# Schematic_R2_5.net
KiCad netlist of a schematic drawn in Altium Designer
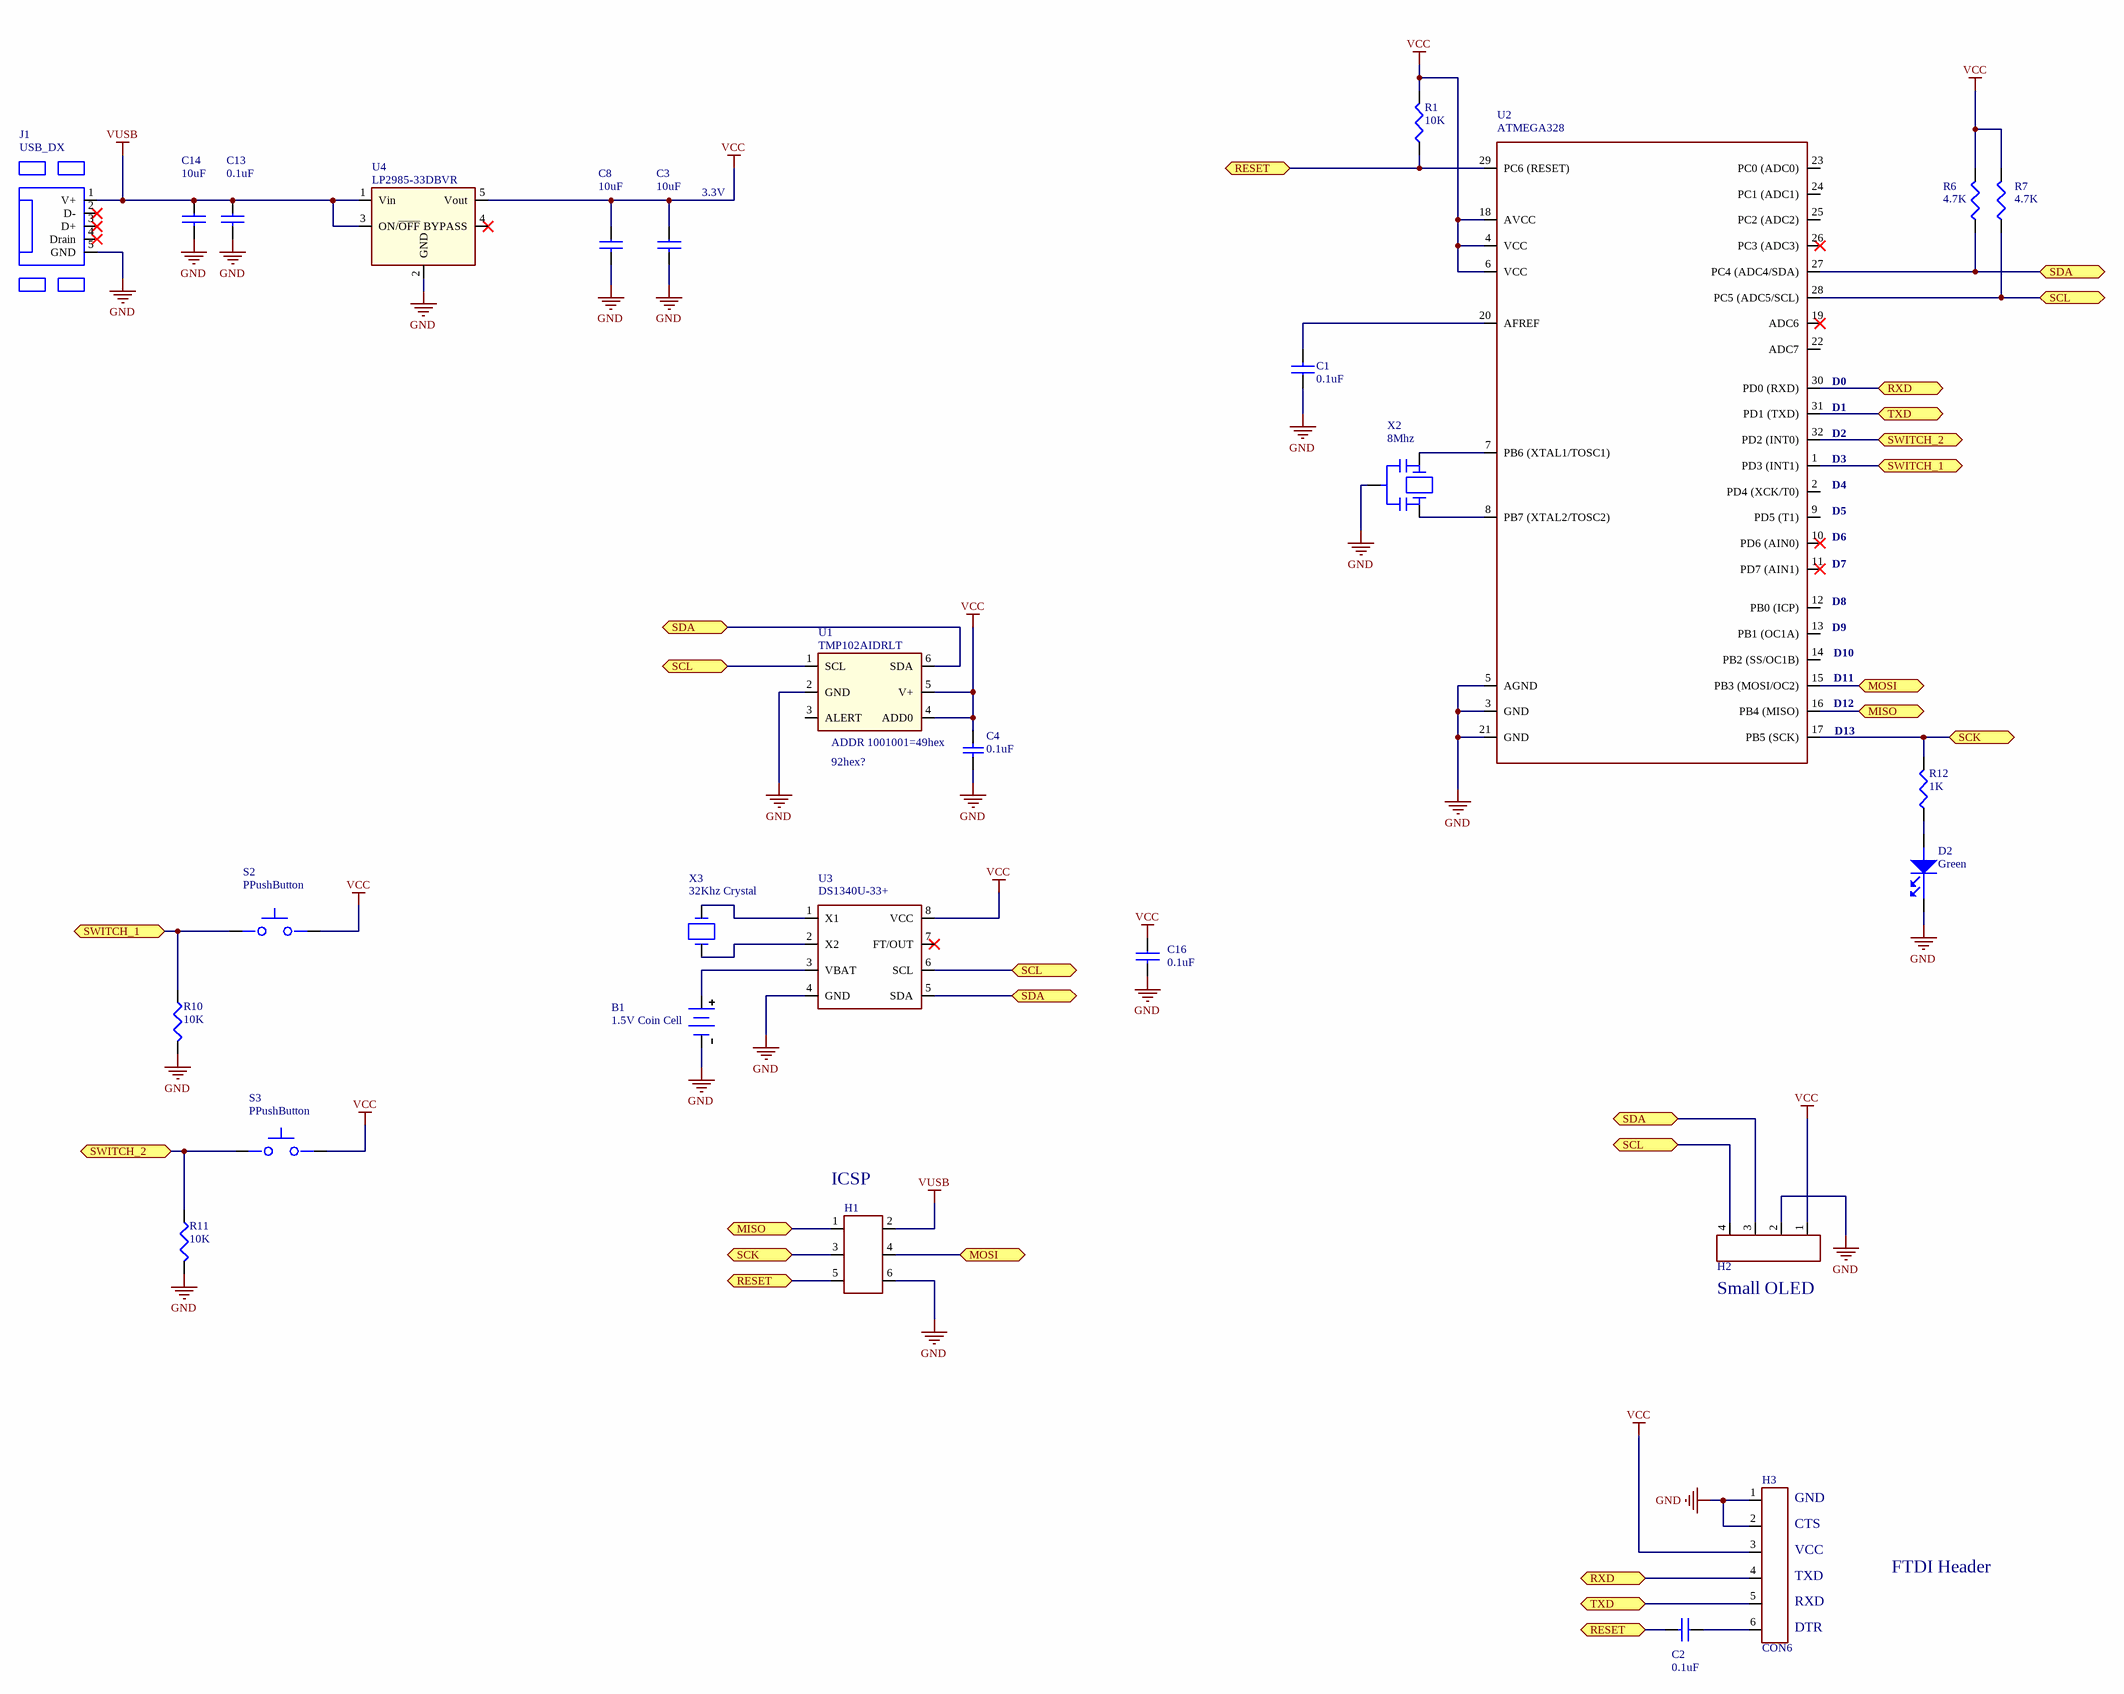
[diagram p0: Schematic_R2.5.SchDoc]

(export (version "E")
  (design (tool "Eeschema 10.0.6"))
  (components
    (comp (ref "B1")
      (value "1.5V Coin Cell")
      (footprint "CR377 Mount")
      (description "Custom CR377 mount")
      (fields (field (name "MANUFACTURER") "Sunbeam") (field (name "Comment") "CR377"))
      (libsource (lib "MAR") (part "CR377"))
    )
    (comp (ref "C1")
      (value "0.1uF")
      (footprint "CAPC1608X90N")
      (description "CAP CER 0.1uF, 0603")
      (libsource (lib "Parts_Library") (part "CAP_0603"))
    )
    (comp (ref "C2")
      (value "0.1uF")
      (footprint "CAPC1608X90N")
      (description "CAP CER 0.1uF, 0603")
      (libsource (lib "Parts_Library") (part "CAP_0603"))
    )
    (comp (ref "C3")
      (value "10uF")
      (footprint "CAPC3216X160N")
      (description "CAP_1206")
      (libsource (lib "MAR") (part "CAP_1206"))
    )
    (comp (ref "C4")
      (value "0.1uF")
      (footprint "CAPC1608X09L")
      (description "CAP CER 0.1UF 50V 10% X7R 0603")
      (fields (field (name "PARTNUMBER") "GRM188R71H104KA93D") (field (name "MANUFACTURER") "Murata"))
      (libsource (lib "Miscellaneous Devices") (part "Cap Semi"))
    )
    (comp (ref "C8")
      (value "10uF")
      (footprint "CAPC3216X160N")
      (description "CAP_1206")
      (libsource (lib "MAR") (part "CAP_1206"))
    )
    (comp (ref "C13")
      (value "0.1uF")
      (footprint "CAPC1608X90N")
      (description "CAP 0603")
      (libsource (lib "Parts_Library") (part "CAP_0603"))
    )
    (comp (ref "C14")
      (value "10uF")
      (footprint "CAPC3216X160N")
      (description "CAP_1206")
      (libsource (lib "MAR") (part "CAP_1206"))
    )
    (comp (ref "C16")
      (value "0.1uF")
      (footprint "CAPC1608X90N")
      (description "CAP CER 0.1uF 0603")
      (libsource (lib "Parts_Library") (part "CAP_0603"))
    )
    (comp (ref "D2")
      (value "Green")
      (footprint "LED1608X55N-YELLOW")
      (description "LED_0603")
      (libsource (lib "Parts_Library") (part "LED_0603"))
    )
    (comp (ref "H1")
      (value "CON3X2")
      (footprint "HDR3X2")
      (description "CONN HEADER 3X2POS .100\" PADS")
      (fields (field (name "PARTNUMBER") "PADS"))
      (libsource (lib "Parts_Library") (part "CON3X2"))
    )
    (comp (ref "H2")
      (value "TSW-104-07-L-S")
      (footprint "HDR1X4-Empty")
      (description "CONN HEADER 4POS .100\" SGL GOLD")
      (fields (field (name "MANUFACTURER") "Samtec"))
      (libsource (lib "Parts_Library") (part "TSW-104-07-L-S"))
    )
    (comp (ref "H3")
      (value "CON6")
      (footprint "HDR1X6")
      (description "CONN HEADER 6POS .100\" PADS")
      (fields (field (name "PARTNUMBER") "PADS"))
      (libsource (lib "MAR") (part "CON6"))
    )
    (comp (ref "J1")
      (value "USB_DX")
      (footprint "USB_DX")
      (description "CONN RECEPT MINIUSB R/A 5POS SMD")
      (libsource (lib "Parts_Library") (part "USB_DX"))
    )
    (comp (ref "R1")
      (value "10K")
      (footprint "RESC1608X55N")
      (description "RES 10K, 0603")
      (libsource (lib "Parts_Library") (part "RES_0603"))
    )
    (comp (ref "R6")
      (value "4.7K")
      (footprint "RESC1608X55N")
      (description "RES 10K, 0603")
      (libsource (lib "Parts_Library") (part "RES_0603"))
    )
    (comp (ref "R7")
      (value "4.7K")
      (footprint "RESC1608X55N")
      (description "RES 10K, 0603")
      (libsource (lib "Parts_Library") (part "RES_0603"))
    )
    (comp (ref "R10")
      (value "10K")
      (footprint "RESC1608X55N")
      (description "RES 10K 0603")
      (libsource (lib "Parts_Library") (part "RES_0603"))
    )
    (comp (ref "R11")
      (value "10K")
      (footprint "RESC1608X55N")
      (description "RES 10K 0603")
      (libsource (lib "Parts_Library") (part "RES_0603"))
    )
    (comp (ref "R12")
      (value "1K")
      (footprint "RESC1608X55N")
      (description "RES 330R, 0603")
      (libsource (lib "Parts_Library") (part "RES_0603"))
    )
    (comp (ref "S2")
      (value "PPushButton")
      (footprint "SWITCH TACTILE RA- DX")
      (description "DX_MINI_TACT_SWITCH_RA")
      (libsource (lib "MAR") (part "DX_MINI_TACT_SWITCH_RA"))
    )
    (comp (ref "S3")
      (value "PPushButton")
      (footprint "SWITCH TACTILE RA- DX")
      (description "DX_MINI_TACT_SWITCH_RA")
      (libsource (lib "MAR") (part "DX_MINI_TACT_SWITCH_RA"))
    )
    (comp (ref "U1")
      (value "TMP102AIDRL")
      (footprint "SOT50P150X130-6N")
      (description "IC DGTL TEMP SENSOR LP SOT-563")
      (fields (field (name "MANUFACTURER") "Texas Instruments") (field (name "PARTNUMBER") "TMP102AIDRLT"))
      (libsource (lib "MAR") (part "TMP102AIDRL"))
    )
    (comp (ref "U2")
      (value "ATMEGA328")
      (footprint "TQFP80P700X700-32N")
      (description "MCU AVR 32K FLASH 32TQFP")
      (fields (field (name "PARTNUMBER") "ATMEGA328P-AU-ND") (field (name "MANUFACTURER") "Atmel"))
      (libsource (lib "Parts_Library") (part "ATMEGA328-AUR"))
    )
    (comp (ref "U3")
      (value "DS1340U-33+")
      (footprint "TSOP65P490X110-8N")
      (description "IC RTC SERIAL 512K 8-TSSOP")
      (fields (field (name "MANUFACTURER") "Maxim"))
      (libsource (lib "Parts_Library") (part "DS1340U-33+"))
    )
    (comp (ref "U4")
      (value "LP2985-33DBVR")
      (footprint "SOT95P280X144-5N")
      (description "IC REG LDO 3.3V .15A SOT23-5")
      (fields (field (name "MANUFACTURER") "Texas Instruments") (field (name "PARTNUMBER") "LP2985-33DBVR"))
      (libsource (lib "MAR") (part "LP2985-33DBVR"))
    )
    (comp (ref "X2")
      (value "8Mhz")
      (footprint "CSTCE")
      (description "CER RESONATOR 8.0MHZ SMD")
      (fields (field (name "PARTNUMBER") "CSTCE8M00G55-R0") (field (name "MANUFACTURER") "Murata"))
      (libsource (lib "Parts_Library") (part "CSTCE8M00G55-R0"))
    )
    (comp (ref "X3")
      (value "32Khz Crystal")
      (footprint "ECS-.327-12.5-34B")
      (description "CRYSTAL 32.768 KHZ 12.5PF SMD")
      (fields (field (name "PARTNUMBER") "ECS-.327-12.5-34B") (field (name "MANUFACTURER") "ECS"))
      (libsource (lib "Parts_Library") (part "ECS-.327-12.5-34B"))
    )
  )
  (nets
    (net (code "1") (name "/MISO") (class "Default")
      (node (ref "H1") (pin "1") (pintype "passive"))
      (node (ref "U2") (pin "16") (pinfunction "PB4_(MISO)_16") (pintype "passive"))
    )
    (net (code "2") (name "/MOSI") (class "Default")
      (node (ref "H1") (pin "4") (pintype "passive"))
      (node (ref "U2") (pin "15") (pinfunction "PB3_(MOSI/OC2)_15") (pintype "passive"))
    )
    (net (code "3") (name "/RESET") (class "Default")
      (node (ref "C2") (pin "2") (pinfunction "2_2") (pintype "passive"))
      (node (ref "H1") (pin "5") (pintype "passive"))
      (node (ref "R1") (pin "1") (pinfunction "1_1") (pintype "passive"))
      (node (ref "U2") (pin "29") (pinfunction "PC6_(RESET)_29") (pintype "passive"))
    )
    (net (code "4") (name "/RXD") (class "Default")
      (node (ref "H3") (pin "4") (pintype "passive"))
      (node (ref "U2") (pin "30") (pinfunction "PD0_(RXD)_30") (pintype "passive"))
    )
    (net (code "5") (name "/SCK") (class "Default")
      (node (ref "H1") (pin "3") (pintype "passive"))
      (node (ref "R12") (pin "2") (pinfunction "2_2") (pintype "passive"))
      (node (ref "U2") (pin "17") (pinfunction "PB5_(SCK)_17") (pintype "passive"))
    )
    (net (code "6") (name "/SCL") (class "Default")
      (node (ref "H2") (pin "4") (pintype "passive"))
      (node (ref "R7") (pin "1") (pinfunction "1_1") (pintype "passive"))
      (node (ref "U1") (pin "1") (pinfunction "SCL_1") (pintype "passive"))
      (node (ref "U2") (pin "28") (pinfunction "PC5_(ADC5/SCL)_28") (pintype "passive"))
      (node (ref "U3") (pin "6") (pinfunction "SCL_6") (pintype "passive"))
    )
    (net (code "7") (name "/SDA") (class "Default")
      (node (ref "H2") (pin "3") (pintype "passive"))
      (node (ref "R6") (pin "1") (pinfunction "1_1") (pintype "passive"))
      (node (ref "U1") (pin "6") (pinfunction "SDA_6") (pintype "passive"))
      (node (ref "U2") (pin "27") (pinfunction "PC4_(ADC4/SDA)_27") (pintype "passive"))
      (node (ref "U3") (pin "5") (pinfunction "SDA_5") (pintype "passive"))
    )
    (net (code "8") (name "/SWITCH_1") (class "Default")
      (node (ref "R10") (pin "1") (pinfunction "1_1") (pintype "passive"))
      (node (ref "S2") (pin "1") (pinfunction "A_1") (pintype "passive"))
      (node (ref "U2") (pin "1") (pinfunction "PD3_(INT1)_1") (pintype "passive"))
    )
    (net (code "9") (name "/SWITCH_2") (class "Default")
      (node (ref "R11") (pin "1") (pinfunction "1_1") (pintype "passive"))
      (node (ref "S3") (pin "2") (pinfunction "B_2") (pintype "passive"))
      (node (ref "U2") (pin "32") (pinfunction "PD2_(INT0)_32") (pintype "passive"))
    )
    (net (code "10") (name "/TXD") (class "Default")
      (node (ref "H3") (pin "5") (pintype "passive"))
      (node (ref "U2") (pin "31") (pinfunction "PD1_(TXD)_31") (pintype "passive"))
    )
    (net (code "11") (name "GND") (class "Default")
      (node (ref "B1") (pin "2") (pinfunction "-_2") (pintype "passive"))
      (node (ref "C1") (pin "1") (pinfunction "1_1") (pintype "passive"))
      (node (ref "C13") (pin "2") (pinfunction "2_2") (pintype "passive"))
      (node (ref "C14") (pin "2") (pinfunction "2_2") (pintype "passive"))
      (node (ref "C16") (pin "2") (pinfunction "2_2") (pintype "passive"))
      (node (ref "C3") (pin "2") (pinfunction "2_2") (pintype "passive"))
      (node (ref "C4") (pin "1") (pinfunction "1_1") (pintype "passive"))
      (node (ref "C8") (pin "2") (pinfunction "2_2") (pintype "passive"))
      (node (ref "D2") (pin "1") (pinfunction "CATHODE_1") (pintype "passive"))
      (node (ref "H1") (pin "6") (pintype "passive"))
      (node (ref "H2") (pin "2") (pintype "passive"))
      (node (ref "H3") (pin "1") (pintype "passive"))
      (node (ref "H3") (pin "2") (pintype "passive"))
      (node (ref "J1") (pin "5") (pinfunction "GND_5") (pintype "power_in"))
      (node (ref "R10") (pin "2") (pinfunction "2_2") (pintype "passive"))
      (node (ref "R11") (pin "2") (pinfunction "2_2") (pintype "passive"))
      (node (ref "U1") (pin "2") (pinfunction "GND_2") (pintype "power_in"))
      (node (ref "U2") (pin "21") (pinfunction "GND_21") (pintype "power_in"))
      (node (ref "U2") (pin "3") (pinfunction "GND_3") (pintype "power_in"))
      (node (ref "U2") (pin "5") (pinfunction "AGND_5") (pintype "power_in"))
      (node (ref "U3") (pin "4") (pinfunction "GND_4") (pintype "passive"))
      (node (ref "U4") (pin "2") (pinfunction "GND_2") (pintype "power_in"))
      (node (ref "X2") (pin "2") (pinfunction "2_2") (pintype "passive"))
    )
    (net (code "12") (name "Net-(B1-+)") (class "Default")
      (node (ref "B1") (pin "1") (pinfunction "+_1") (pintype "passive"))
      (node (ref "U3") (pin "3") (pinfunction "VBAT_3") (pintype "passive"))
    )
    (net (code "13") (name "Net-(C2-Pad1)") (class "Default")
      (node (ref "C2") (pin "1") (pinfunction "1_1") (pintype "passive"))
      (node (ref "H3") (pin "6") (pintype "passive"))
    )
    (net (code "14") (name "Net-(D2-ANODE)") (class "Default")
      (node (ref "D2") (pin "2") (pinfunction "ANODE_2") (pintype "passive"))
      (node (ref "R12") (pin "1") (pinfunction "1_1") (pintype "passive"))
    )
    (net (code "15") (name "Net-(U2-AFREF)") (class "Default")
      (node (ref "C1") (pin "2") (pinfunction "2_2") (pintype "passive"))
      (node (ref "U2") (pin "20") (pinfunction "AFREF_20") (pintype "passive"))
    )
    (net (code "16") (name "Net-(U2-PB6_(XTAL1{slash}TOSC1))") (class "Default")
      (node (ref "U2") (pin "7") (pinfunction "PB6_(XTAL1/TOSC1)_7") (pintype "passive"))
      (node (ref "X2") (pin "1") (pinfunction "1_1") (pintype "passive"))
    )
    (net (code "17") (name "Net-(U2-PB7_(XTAL2{slash}TOSC2))") (class "Default")
      (node (ref "U2") (pin "8") (pinfunction "PB7_(XTAL2/TOSC2)_8") (pintype "passive"))
      (node (ref "X2") (pin "3") (pinfunction "3_3") (pintype "passive"))
    )
    (net (code "18") (name "Net-(U3-X1)") (class "Default")
      (node (ref "U3") (pin "1") (pinfunction "X1_1") (pintype "passive"))
      (node (ref "X3") (pin "1") (pinfunction "1_1") (pintype "passive"))
    )
    (net (code "19") (name "Net-(U3-X2)") (class "Default")
      (node (ref "U3") (pin "2") (pinfunction "X2_2") (pintype "passive"))
      (node (ref "X3") (pin "2") (pinfunction "2_2") (pintype "passive"))
    )
    (net (code "20") (name "VCC") (class "Default")
      (node (ref "C16") (pin "1") (pinfunction "1_1") (pintype "passive"))
      (node (ref "C3") (pin "1") (pinfunction "1_1") (pintype "passive"))
      (node (ref "C4") (pin "2") (pinfunction "2_2") (pintype "passive"))
      (node (ref "C8") (pin "1") (pinfunction "1_1") (pintype "passive"))
      (node (ref "H2") (pin "1") (pintype "passive"))
      (node (ref "H3") (pin "3") (pintype "passive"))
      (node (ref "R1") (pin "2") (pinfunction "2_2") (pintype "passive"))
      (node (ref "R6") (pin "2") (pinfunction "2_2") (pintype "passive"))
      (node (ref "R7") (pin "2") (pinfunction "2_2") (pintype "passive"))
      (node (ref "S2") (pin "2") (pinfunction "B_2") (pintype "passive"))
      (node (ref "S3") (pin "1") (pinfunction "A_1") (pintype "passive"))
      (node (ref "U1") (pin "4") (pinfunction "ADD0_4") (pintype "passive"))
      (node (ref "U1") (pin "5") (pinfunction "V+_5") (pintype "power_in"))
      (node (ref "U2") (pin "18") (pinfunction "AVCC_18") (pintype "power_in"))
      (node (ref "U2") (pin "4") (pinfunction "VCC_4") (pintype "power_in"))
      (node (ref "U2") (pin "6") (pinfunction "VCC_6") (pintype "power_in"))
      (node (ref "U3") (pin "8") (pinfunction "VCC_8") (pintype "power_in"))
      (node (ref "U4") (pin "5") (pinfunction "Vout_5") (pintype "passive"))
    )
    (net (code "21") (name "VUSB") (class "Default")
      (node (ref "C13") (pin "1") (pinfunction "1_1") (pintype "passive"))
      (node (ref "C14") (pin "1") (pinfunction "1_1") (pintype "passive"))
      (node (ref "H1") (pin "2") (pintype "passive"))
      (node (ref "J1") (pin "1") (pinfunction "V+_1") (pintype "power_in"))
      (node (ref "U4") (pin "1") (pinfunction "Vin_1") (pintype "passive"))
      (node (ref "U4") (pin "3") (pinfunction "ON/~{OFF}_3") (pintype "passive"))
    )
    (net (code "22") (name "unconnected-(J1-D+-Pad3)") (class "Default")
      (node (ref "J1") (pin "3") (pinfunction "D+_3") (pintype "passive+no_connect"))
    )
    (net (code "23") (name "unconnected-(J1-D--Pad2)") (class "Default")
      (node (ref "J1") (pin "2") (pinfunction "D-_2") (pintype "passive+no_connect"))
    )
    (net (code "24") (name "unconnected-(J1-Drain-Pad4)") (class "Default")
      (node (ref "J1") (pin "4") (pinfunction "Drain_4") (pintype "passive+no_connect"))
    )
    (net (code "25") (name "unconnected-(U1-ALERT-Pad3)") (class "Default")
      (node (ref "U1") (pin "3") (pinfunction "ALERT_3") (pintype "passive"))
    )
    (net (code "26") (name "unconnected-(U2-ADC6-Pad19)") (class "Default")
      (node (ref "U2") (pin "19") (pinfunction "ADC6_19") (pintype "passive+no_connect"))
    )
    (net (code "27") (name "unconnected-(U2-ADC7-Pad22)") (class "Default")
      (node (ref "U2") (pin "22") (pinfunction "ADC7_22") (pintype "passive"))
    )
    (net (code "28") (name "unconnected-(U2-PB0_(ICP)-Pad12)") (class "Default")
      (node (ref "U2") (pin "12") (pinfunction "PB0_(ICP)_12") (pintype "passive"))
    )
    (net (code "29") (name "unconnected-(U2-PB1_(OC1A)-Pad13)") (class "Default")
      (node (ref "U2") (pin "13") (pinfunction "PB1_(OC1A)_13") (pintype "passive"))
    )
    (net (code "30") (name "unconnected-(U2-PB2_(SS{slash}OC1B)-Pad14)") (class "Default")
      (node (ref "U2") (pin "14") (pinfunction "PB2_(SS/OC1B)_14") (pintype "passive"))
    )
    (net (code "31") (name "unconnected-(U2-PC0_(ADC0)-Pad23)") (class "Default")
      (node (ref "U2") (pin "23") (pinfunction "PC0_(ADC0)_23") (pintype "passive"))
    )
    (net (code "32") (name "unconnected-(U2-PC1_(ADC1)-Pad24)") (class "Default")
      (node (ref "U2") (pin "24") (pinfunction "PC1_(ADC1)_24") (pintype "passive"))
    )
    (net (code "33") (name "unconnected-(U2-PC2_(ADC2)-Pad25)") (class "Default")
      (node (ref "U2") (pin "25") (pinfunction "PC2_(ADC2)_25") (pintype "passive"))
    )
    (net (code "34") (name "unconnected-(U2-PC3_(ADC3)-Pad26)") (class "Default")
      (node (ref "U2") (pin "26") (pinfunction "PC3_(ADC3)_26") (pintype "passive+no_connect"))
    )
    (net (code "35") (name "unconnected-(U2-PD4_(XCK{slash}T0)-Pad2)") (class "Default")
      (node (ref "U2") (pin "2") (pinfunction "PD4_(XCK/T0)_2") (pintype "passive"))
    )
    (net (code "36") (name "unconnected-(U2-PD5_(T1)-Pad9)") (class "Default")
      (node (ref "U2") (pin "9") (pinfunction "PD5_(T1)_9") (pintype "passive"))
    )
    (net (code "37") (name "unconnected-(U2-PD6_(AIN0)-Pad10)") (class "Default")
      (node (ref "U2") (pin "10") (pinfunction "PD6_(AIN0)_10") (pintype "passive+no_connect"))
    )
    (net (code "38") (name "unconnected-(U2-PD7_(AIN1)-Pad11)") (class "Default")
      (node (ref "U2") (pin "11") (pinfunction "PD7_(AIN1)_11") (pintype "passive+no_connect"))
    )
    (net (code "39") (name "unconnected-(U3-FT{slash}OUT-Pad7)") (class "Default")
      (node (ref "U3") (pin "7") (pinfunction "FT/OUT_7") (pintype "passive+no_connect"))
    )
    (net (code "40") (name "unconnected-(U4-BYPASS-Pad4)") (class "Default")
      (node (ref "U4") (pin "4") (pinfunction "BYPASS_4") (pintype "passive+no_connect"))
    )
  )
)
